# CPU_Clock.net
KiCad netlist of a schematic drawn in Altium Designer
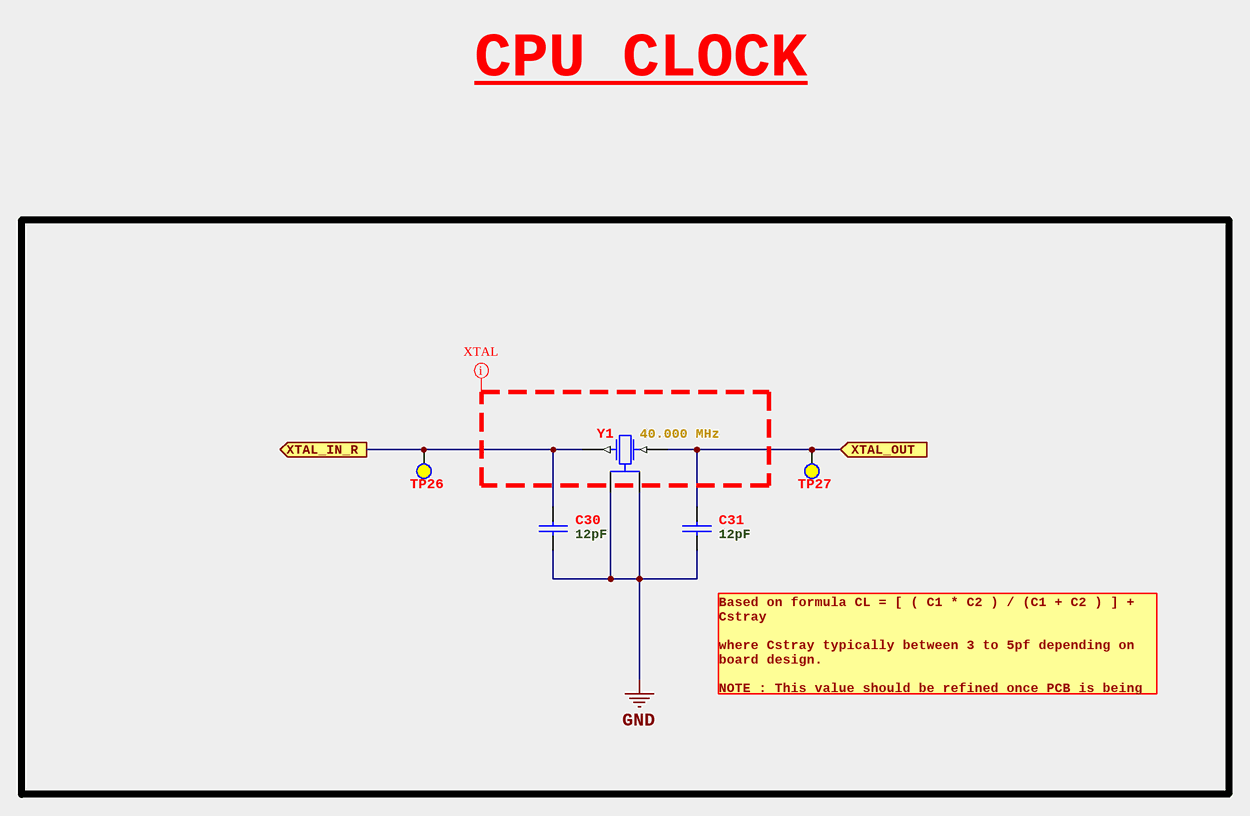
[diagram p0: CPU Clock.SchDoc]

(export (version "E")
  (design (tool "Eeschema 10.0.6"))
  (components
    (comp (ref "C30")
      (value "12pF")
      (footprint "CAP_0603")
      (description "12 pF ±5% 50V Ceramic Capacitor C0G, NP0 0603 (1608 Metric)")
      (fields
        (field (name "MANUFACTURER") "Yageo")
        (field (name "MANUFACTURER PART NUMBER") "CC0603JRNPO9BN120")
      )
      (libsource (lib "Cellar Watchdog") (part "CAP_12pf-50V-5%_0603"))
    )
    (comp (ref "C31")
      (value "12pF")
      (footprint "CAP_0603")
      (description "12 pF ±5% 50V Ceramic Capacitor C0G, NP0 0603 (1608 Metric)")
      (fields
        (field (name "MANUFACTURER") "Yageo")
        (field (name "MANUFACTURER PART NUMBER") "CC0603JRNPO9BN120")
      )
      (libsource (lib "Cellar Watchdog") (part "CAP_12pf-50V-5%_0603"))
    )
    (comp (ref "TP26")
      (value "CPU 40MHz IN")
      (footprint "TEST POINT HOLE")
      (description "PCB Test Point")
      (libsource (lib "Cellar Watchdog") (part "Test Point"))
    )
    (comp (ref "TP27")
      (value "CPU 40MHz OUT")
      (footprint "TEST POINT HOLE")
      (description "PCB Test Point")
      (libsource (lib "Cellar Watchdog") (part "Test Point"))
    )
    (comp (ref "Y1")
      (value "ECS-400-10-37B2-CKY-TR")
      (footprint "XTAL_ECS-400-10-37B2")
      (description "40 MHz ±10ppm Crystal 10pF 40 Ohms 4-SMD, No Lead")
      (fields (field (name "MANUFACTURER") "ECS International") (field (name "FREQUENCY") "40.000 MHz"))
      (libsource (lib "Cellar Watchdog") (part "XTAL_40.000MHz-10pF_4-SMD"))
    )
  )
  (nets
    (net (code "1") (name "/XTAL_IN_R") (class "Default")
      (node (ref "C30") (pin "1") (pinfunction "1_1") (pintype "passive"))
      (node (ref "TP26") (pin "TP") (pinfunction "TP_TP") (pintype "passive"))
      (node (ref "Y1") (pin "1") (pinfunction "In/Out_1") (pintype "output"))
    )
    (net (code "2") (name "/XTAL_OUT") (class "Default")
      (node (ref "C31") (pin "1") (pinfunction "1_1") (pintype "passive"))
      (node (ref "TP27") (pin "TP") (pinfunction "TP_TP") (pintype "passive"))
      (node (ref "Y1") (pin "3") (pinfunction "Out/In_3") (pintype "input"))
    )
    (net (code "3") (name "GND") (class "Default")
      (node (ref "C30") (pin "2") (pinfunction "2_2") (pintype "passive"))
      (node (ref "C31") (pin "2") (pinfunction "2_2") (pintype "passive"))
      (node (ref "Y1") (pin "2") (pinfunction "GND_2") (pintype "power_in"))
      (node (ref "Y1") (pin "4") (pinfunction "GND_4") (pintype "power_in"))
    )
  )
)
